# Kajtu_-DSP_power_supply.net
KiCad netlist of a schematic drawn in Altium Designer
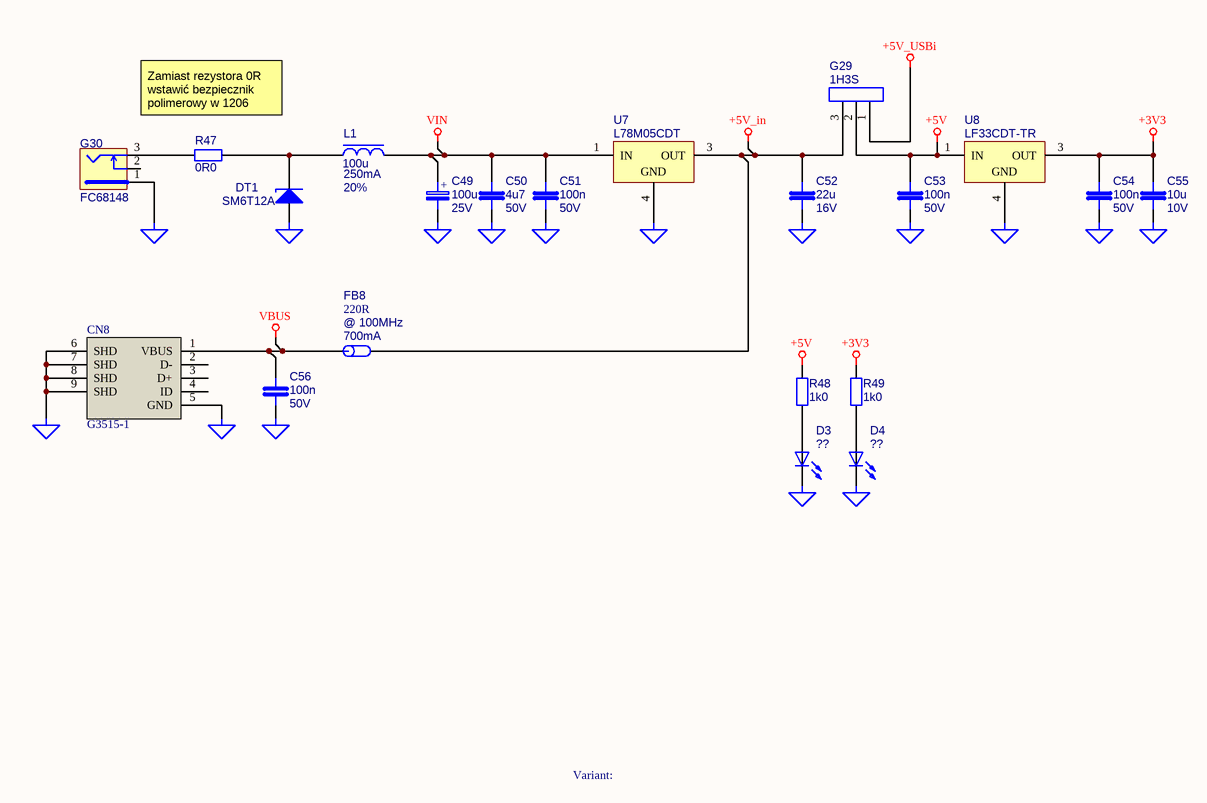
[diagram p0: Kajtuś-DSP_power_supply.SchDoc]

(export (version "E")
  (design (tool "Eeschema 10.0.6"))
  (components
    (comp (ref "C49")
      (value "100u")
      (footprint "CAPPRD-035-W06-D063-H115")
      (description "Aluminum Electrolytic Capacitor, D6.3, H11.5, 100u, 25V, 20%")
      (fields (field (name "TOLERANCE") "20%") (field (name "VOLTAGE") "25V"))
      (libsource (lib "MM_capacitors") (part "CE_CAPPRD-035-W06-D063-H115_100u_25V"))
    )
    (comp (ref "C50")
      (value "4u7")
      (footprint "C_1206")
      (description "Ceramic SMD 1206 Capacitor, 4u7, 50V, 10%, X7R")
      (fields (field (name "TOLERANCE") "10%") (field (name "VOLTAGE") "50V"))
      (libsource (lib "MM_capacitors") (part "C_1206_4u7_50V_X7R"))
    )
    (comp (ref "C51")
      (value "100n")
      (footprint "C_0603")
      (description "Ceramic SMD 0603 Capacitor, 100n, 50V, X7R")
      (fields (field (name "TOLERANCE") "10%") (field (name "VOLTAGE") "50V"))
      (libsource (lib "AD_ostry_intlib") (part "C_0603_100n_50V_X7R"))
    )
    (comp (ref "C52")
      (value "22u")
      (footprint "C_1206")
      (description "Ceramic SMD 1206 Capacitor, 22u, 16V, 10%, X5R")
      (fields (field (name "TOLERANCE") "10%") (field (name "VOLTAGE") "16V"))
      (libsource (lib "MM_capacitors") (part "C_1206_22u_16V_X5R"))
    )
    (comp (ref "C53")
      (value "100n")
      (footprint "C_0603")
      (description "Ceramic SMD 0603 Capacitor, 100n, 50V, X7R")
      (fields (field (name "TOLERANCE") "10%") (field (name "VOLTAGE") "50V"))
      (libsource (lib "AD_ostry_intlib") (part "C_0603_100n_50V_X7R"))
    )
    (comp (ref "C54")
      (value "100n")
      (footprint "C_0603")
      (description "Ceramic SMD 0603 Capacitor, 100n, 50V, X7R")
      (fields (field (name "TOLERANCE") "10%") (field (name "VOLTAGE") "50V"))
      (libsource (lib "AD_ostry_intlib") (part "C_0603_100n_50V_X7R"))
    )
    (comp (ref "C55")
      (value "10u")
      (footprint "C_0805")
      (description "Ceramic SMD 0805 Capacitor, 10u, 10V, X5R")
      (fields (field (name "TOLERANCE") "10%") (field (name "VOLTAGE") "10V"))
      (libsource (lib "MM_capacitors") (part "C_0805_10u_10V_X5R"))
    )
    (comp (ref "C56")
      (value "100n")
      (footprint "C_0603")
      (description "Ceramic SMD 0603 Capacitor, 100n, 50V, X7R")
      (fields (field (name "TOLERANCE") "10%") (field (name "VOLTAGE") "50V"))
      (libsource (lib "AD_ostry_intlib") (part "C_0603_100n_50V_X7R"))
    )
    (comp (ref "CN8")
      (value "G3515-1")
      (footprint "CN_USB_mini_B_G3515-1")
      (description "Mini USB 1u\" S/G W/O Mark S-Type")
      (fields (field (name "OZNACZENIE") "G3515-1"))
      (libsource (lib "MM_connectors") (part "CN_USB_mini-B_G3515-1"))
    )
    (comp (ref "D3")
      (value "??")
      (footprint "LED_0805_G")
      (description "Dioda LED SMD")
      (fields (field (name "PART NUMBER") "LED_SMD_generic"))
      (libsource (lib "AD_ostry_intlib") (part "LED_SMD_generic"))
    )
    (comp (ref "D4")
      (value "??")
      (footprint "LED_0805_G")
      (description "Dioda LED SMD")
      (fields (field (name "PART NUMBER") "LED_SMD_generic"))
      (libsource (lib "AD_ostry_intlib") (part "LED_SMD_generic"))
    )
    (comp (ref "DT1")
      (value "SM6T12A")
      (footprint "SMB")
      (description "Dioda Transil, 12V, 600W @ 10/1000us, jednokierunkowa")
      (fields (field (name "VOLTAGE") "33V") (field (name "MANUFACTURER") "Vishay"))
      (libsource (lib "MM_diodes") (part "DT_SMB_SM6T12A"))
    )
    (comp (ref "FB8")
      (value "220R")
      (footprint "FB_0603")
      (description "Ferrite Bead")
      (fields (field (name "FREQUENCY") "@ 100MHz") (field (name "CURRENT") "700mA"))
      (libsource (lib "MM_discrete") (part "FB_0603_220R_100MHz_700mA"))
    )
    (comp (ref "G29")
      (value "1H3S")
      (footprint "1H3S_FHS")
      (description "Listwa jednorzędowa, 1x3 piny, raster 2,54mm")
      (fields (field (name "PART NUMBER") "G_1H3S") (field (name "MANUFACTURER") "generic"))
      (libsource (lib "AD_ostry_intlib") (part "G_1H3S"))
    )
    (comp (ref "G30")
      (value "FC68148")
      (footprint "CN_DC_PWR_5.5x2.1_FC68148")
      (description "DC Power Socket, 5.5mm x 2.1mm, with switch")
      (libsource (lib "MM_connectors") (part "CN_DC_PWR_5.5x2.1_FC68148"))
    )
    (comp (ref "L1")
      (value "100u")
      (footprint "Walsin_303015")
      (description "Shielded SMD Power Inductors - WLPN303015 Series")
      (fields
        (field (name "MANUFACTURER") "Walsin")
        (field (name "MANUFACTURER PART NUMBER") "WLPN303015M101PB")
        (field (name "TOLERANCE") "20%")
        (field (name "CURRENT_RMS") "250mA")
      )
      (libsource (lib "MM_inductors") (part "L_SMD_303015_WLPN303015M101PB_100u_250mA_20%"))
    )
    (comp (ref "R47")
      (value "0R0")
      (footprint "R_1206")
      (description "Rezystor SMD")
      (fields (field (name "PART NUMBER") "R_1206_0R0_5%") (field (name "MANUFACTURER") "Royal Ohm"))
      (libsource (lib "AD_ostry_intlib") (part "R_1206_0R0_5%"))
    )
    (comp (ref "R48")
      (value "1k0")
      (footprint "R_0603_MA")
      (description "Rezystor SMD")
      (fields (field (name "PART NUMBER") "R_0603_1k0_5%") (field (name "MANUFACTURER") "Royal Ohm"))
      (libsource (lib "AD_ostry_intlib") (part "R_0603_1k0_5%"))
    )
    (comp (ref "R49")
      (value "1k0")
      (footprint "R_0603_MA")
      (description "Rezystor SMD")
      (fields (field (name "PART NUMBER") "R_0603_1k0_5%") (field (name "MANUFACTURER") "Royal Ohm"))
      (libsource (lib "AD_ostry_intlib") (part "R_0603_1k0_5%"))
    )
    (comp (ref "U7")
      (value "L78M05CDT")
      (footprint "TO-252")
      (description "Positive Voltage Regulator")
      (fields (field (name "PUBLISHER") "Altium Limited"))
      (libsource (lib "ST Power Mgt Voltage Regulator") (part "L78M05CDT"))
    )
    (comp (ref "U8")
      (value "LF33CDT-TR")
      (footprint "TO-252_M")
      (description "500mA, Very Low Drop (0.45V) Voltage Regulator, 3.3V, 3-Pin DPAK, Tape and Reel")
      (libsource (lib "STMicroelectronics Power Management Linear Regulator") (part "LF33CDT-TR"))
    )
  )
  (nets
    (net (code "1") (name "+3V3") (class "Default")
      (node (ref "C54") (pin "1") (pinfunction "1_1") (pintype "passive"))
      (node (ref "C55") (pin "1") (pinfunction "1_1") (pintype "passive"))
      (node (ref "R49") (pin "1") (pinfunction "1_1") (pintype "passive"))
      (node (ref "U8") (pin "3") (pinfunction "OUT_3") (pintype "power_in"))
    )
    (net (code "2") (name "+5V") (class "Default")
      (node (ref "C53") (pin "1") (pinfunction "1_1") (pintype "passive"))
      (node (ref "G29") (pin "2") (pinfunction "2_2") (pintype "passive"))
      (node (ref "R48") (pin "1") (pinfunction "1_1") (pintype "passive"))
      (node (ref "U8") (pin "1") (pinfunction "IN_1") (pintype "power_in"))
    )
    (net (code "3") (name "+5V_USBi") (class "Default")
      (node (ref "G29") (pin "1") (pinfunction "1_1") (pintype "passive"))
    )
    (net (code "4") (name "+5V_in") (class "Default")
      (node (ref "C52") (pin "1") (pinfunction "1_1") (pintype "passive"))
      (node (ref "FB8") (pin "2") (pinfunction "2_2") (pintype "passive"))
      (node (ref "G29") (pin "3") (pinfunction "3_3") (pintype "passive"))
      (node (ref "U7") (pin "3") (pinfunction "OUT_3") (pintype "power_in"))
    )
    (net (code "5") (name "GND") (class "Default")
      (node (ref "C49") (pin "2") (pinfunction "2_2") (pintype "passive"))
      (node (ref "C50") (pin "2") (pinfunction "2_2") (pintype "passive"))
      (node (ref "C51") (pin "2") (pinfunction "2_2") (pintype "passive"))
      (node (ref "C52") (pin "2") (pinfunction "2_2") (pintype "passive"))
      (node (ref "C53") (pin "2") (pinfunction "2_2") (pintype "passive"))
      (node (ref "C54") (pin "2") (pinfunction "2_2") (pintype "passive"))
      (node (ref "C55") (pin "2") (pinfunction "2_2") (pintype "passive"))
      (node (ref "C56") (pin "2") (pinfunction "2_2") (pintype "passive"))
      (node (ref "CN8") (pin "5") (pinfunction "GND_5") (pintype "passive"))
      (node (ref "CN8") (pin "6") (pinfunction "SHD_6") (pintype "passive"))
      (node (ref "CN8") (pin "7") (pinfunction "SHD_7") (pintype "passive"))
      (node (ref "CN8") (pin "8") (pinfunction "SHD_8") (pintype "passive"))
      (node (ref "CN8") (pin "9") (pinfunction "SHD_9") (pintype "passive"))
      (node (ref "D3") (pin "2") (pinfunction "K_2") (pintype "passive"))
      (node (ref "D4") (pin "2") (pinfunction "K_2") (pintype "passive"))
      (node (ref "DT1") (pin "2") (pinfunction "A_2") (pintype "passive"))
      (node (ref "G30") (pin "1") (pinfunction "1_1") (pintype "passive"))
      (node (ref "U7") (pin "4") (pinfunction "GND_4") (pintype "power_in"))
      (node (ref "U8") (pin "4") (pinfunction "GND_4") (pintype "power_in"))
    )
    (net (code "6") (name "Net-(D3-A)") (class "Default")
      (node (ref "D3") (pin "1") (pinfunction "A_1") (pintype "passive"))
      (node (ref "R48") (pin "2") (pinfunction "2_2") (pintype "passive"))
    )
    (net (code "7") (name "Net-(D4-A)") (class "Default")
      (node (ref "D4") (pin "1") (pinfunction "A_1") (pintype "passive"))
      (node (ref "R49") (pin "2") (pinfunction "2_2") (pintype "passive"))
    )
    (net (code "8") (name "Net-(DT1-C)") (class "Default")
      (node (ref "DT1") (pin "1") (pinfunction "C_1") (pintype "passive"))
      (node (ref "L1") (pin "1") (pinfunction "1_1") (pintype "passive"))
      (node (ref "R47") (pin "2") (pinfunction "2_2") (pintype "passive"))
    )
    (net (code "9") (name "Net-(G30-Pad3)") (class "Default")
      (node (ref "G30") (pin "3") (pinfunction "3_3") (pintype "passive"))
      (node (ref "R47") (pin "1") (pinfunction "1_1") (pintype "passive"))
    )
    (net (code "10") (name "VBUS") (class "Default")
      (node (ref "C56") (pin "1") (pinfunction "1_1") (pintype "passive"))
      (node (ref "CN8") (pin "1") (pinfunction "VBUS_1") (pintype "passive"))
      (node (ref "FB8") (pin "1") (pinfunction "1_1") (pintype "passive"))
    )
    (net (code "11") (name "VIN") (class "Default")
      (node (ref "C49") (pin "1") (pinfunction "1_1") (pintype "passive"))
      (node (ref "C50") (pin "1") (pinfunction "1_1") (pintype "passive"))
      (node (ref "C51") (pin "1") (pinfunction "1_1") (pintype "passive"))
      (node (ref "L1") (pin "2") (pinfunction "2_2") (pintype "passive"))
      (node (ref "U7") (pin "1") (pinfunction "IN_1") (pintype "power_in"))
    )
    (net (code "12") (name "unconnected-(CN8-D+-Pad3)") (class "Default")
      (node (ref "CN8") (pin "3") (pinfunction "D+_3") (pintype "passive"))
    )
    (net (code "13") (name "unconnected-(CN8-D--Pad2)") (class "Default")
      (node (ref "CN8") (pin "2") (pinfunction "D-_2") (pintype "passive"))
    )
    (net (code "14") (name "unconnected-(CN8-ID-Pad4)") (class "Default")
      (node (ref "CN8") (pin "4") (pinfunction "ID_4") (pintype "passive"))
    )
    (net (code "15") (name "unconnected-(G30-Pad2)") (class "Default")
      (node (ref "G30") (pin "2") (pinfunction "2_2") (pintype "passive"))
    )
  )
)
